# hw_tutorial.net
KiCad netlist of a schematic drawn in Altium Designer
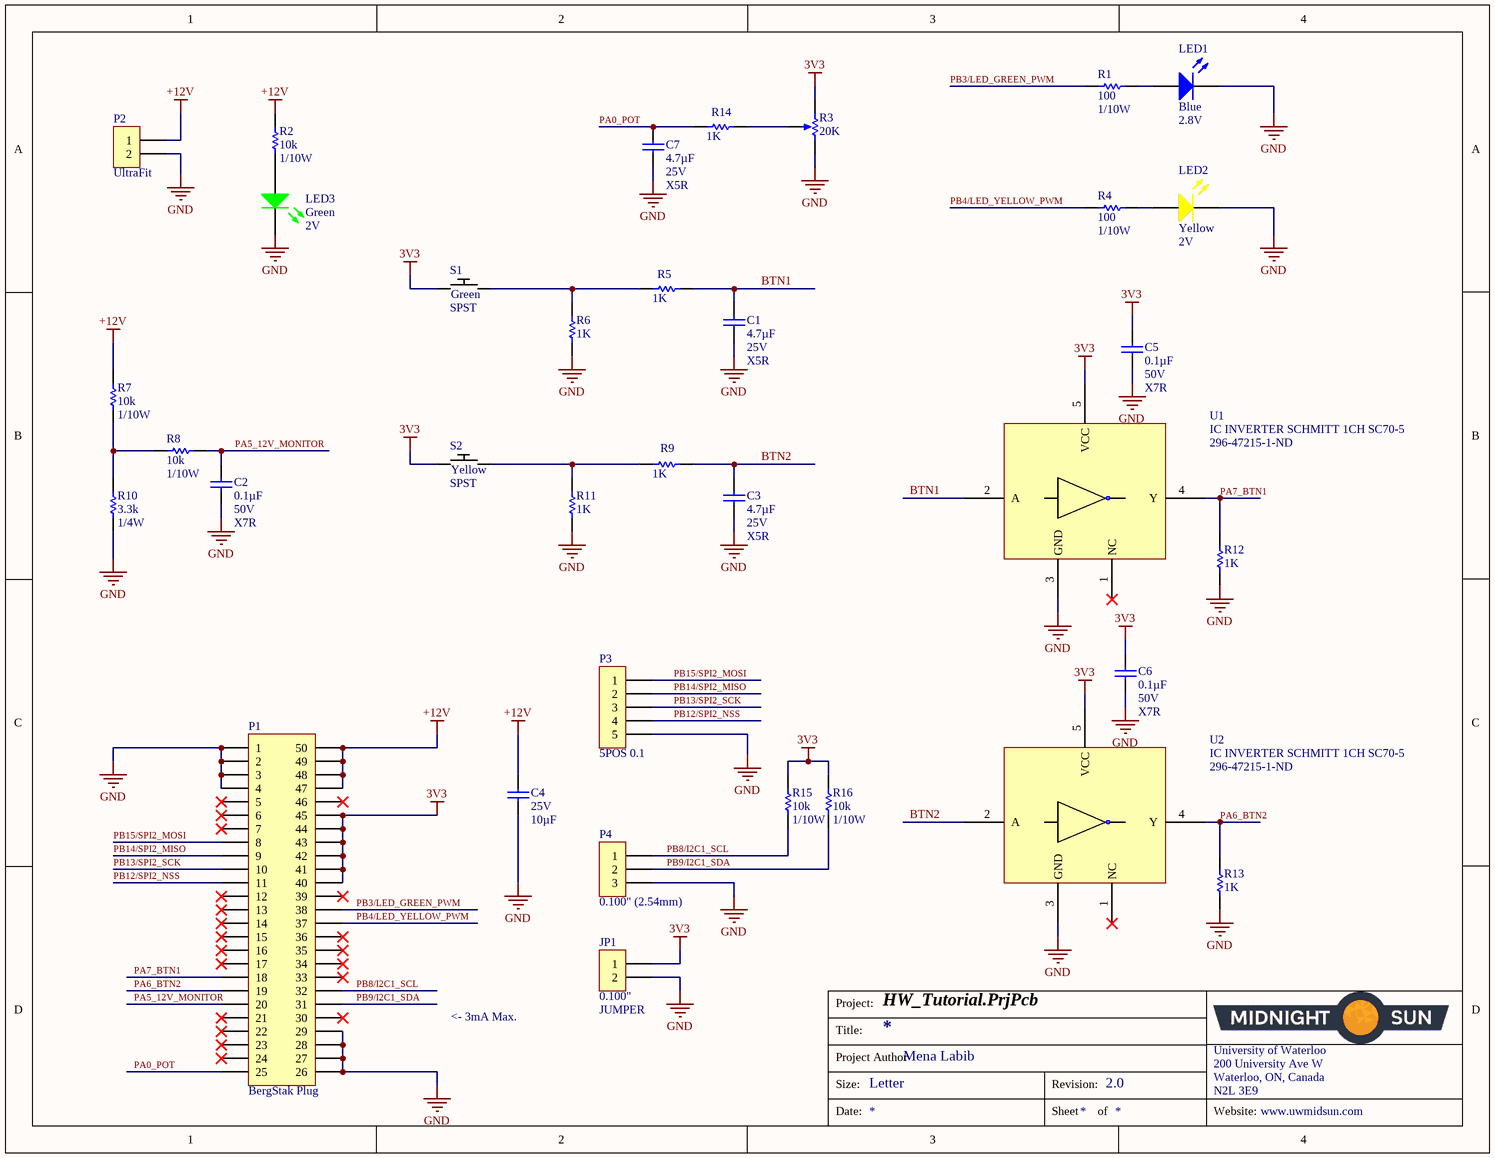
[diagram p0: hw_tutorial.SchDoc]

(export (version "E")
  (design (tool "Eeschema 10.0.6"))
  (components
    (comp (ref "C1")
      (value "CAP CER 4.7UF 25V 10% X5R 0603")
      (footprint "CAP, 0603")
      (description "4.7µF ±10% 25V Ceramic Capacitor X5R 0603 (1608 Metric)")
      (fields
        (field (name "TOLERANCE") "±10%")
        (field (name "CAPACITANCE") "4.7µF")
        (field (name "VOLTAGE") "25V")
        (field (name "TEMPERATURE COEFFICIENT") "X5R")
      )
      (libsource (lib "Schematic Diagrams") (part "CAP CER 4.7UF 25V 10% X5R 0603"))
    )
    (comp (ref "C2")
      (value "CAP CER 0.1UF 50V 10% X7R 0603")
      (footprint "CAP, 0603")
      (description "0.10µF ±10% 50V Ceramic Capacitor X7R 0603 (1608 Metric)")
      (fields
        (field (name "TOLERANCE") "±10%")
        (field (name "CAPACITANCE") "0.1µF")
        (field (name "VOLTAGE") "50V")
        (field (name "TEMPERATURE COEFFICIENT") "X7R")
      )
      (libsource (lib "Schematic Diagrams") (part "CAP CER 0.1UF 50V 10% X7R 0603"))
    )
    (comp (ref "C3")
      (value "CAP CER 4.7UF 25V 10% X5R 0603")
      (footprint "CAP, 0603")
      (description "4.7µF ±10% 25V Ceramic Capacitor X5R 0603 (1608 Metric)")
      (fields
        (field (name "TOLERANCE") "±10%")
        (field (name "CAPACITANCE") "4.7µF")
        (field (name "VOLTAGE") "25V")
        (field (name "TEMPERATURE COEFFICIENT") "X5R")
      )
      (libsource (lib "Schematic Diagrams") (part "CAP CER 4.7UF 25V 10% X5R 0603"))
    )
    (comp (ref "C4")
      (value "CAP CER 10uF 25V 10% X5R 0805")
      (footprint "CAP, 0805")
      (description "10µF ±10% 25V Ceramic Capacitor X5R 0805 (2012 Metric)")
      (fields
        (field (name "MANUFACTURER") "Murata Electronics North America")
        (field (name "MANUFACTURER PART NUMBER") "GRM21BR61E106KA73L")
        (field (name "VOLTAGE - RATED") "25V")
        (field (name "CAPACITANCE") "10µF")
      )
      (libsource (lib "Schematic Diagrams") (part "CAP CER 10uF 25V 10% X5R 0805"))
    )
    (comp (ref "C5")
      (value "CAP CER 0.1UF 50V 10% X7R 0603")
      (footprint "CAP, 0603")
      (description "0.10µF ±10% 50V Ceramic Capacitor X7R 0603 (1608 Metric)")
      (fields
        (field (name "TOLERANCE") "±10%")
        (field (name "CAPACITANCE") "0.1µF")
        (field (name "VOLTAGE") "50V")
        (field (name "TEMPERATURE COEFFICIENT") "X7R")
      )
      (libsource (lib "Schematic Diagrams") (part "CAP CER 0.1UF 50V 10% X7R 0603"))
    )
    (comp (ref "C6")
      (value "CAP CER 0.1UF 50V 10% X7R 0603")
      (footprint "CAP, 0603")
      (description "0.10µF ±10% 50V Ceramic Capacitor X7R 0603 (1608 Metric)")
      (fields
        (field (name "TOLERANCE") "±10%")
        (field (name "CAPACITANCE") "0.1µF")
        (field (name "VOLTAGE") "50V")
        (field (name "TEMPERATURE COEFFICIENT") "X7R")
      )
      (libsource (lib "Schematic Diagrams") (part "CAP CER 0.1UF 50V 10% X7R 0603"))
    )
    (comp (ref "C7")
      (value "CAP CER 4.7UF 25V 10% X5R 0603")
      (footprint "CAP, 0603")
      (description "4.7µF ±10% 25V Ceramic Capacitor X5R 0603 (1608 Metric)")
      (fields
        (field (name "TOLERANCE") "±10%")
        (field (name "CAPACITANCE") "4.7µF")
        (field (name "VOLTAGE") "25V")
        (field (name "TEMPERATURE COEFFICIENT") "X5R")
      )
      (libsource (lib "Schematic Diagrams") (part "CAP CER 4.7UF 25V 10% X5R 0603"))
    )
    (comp (ref "JP1")
      (value "JUMPER")
      (footprint "CONN, 2POS JUMPER 0.1\"")
      (description "2 Positions Header Connector Through Hole Gold")
      (fields
        (field (name "MANUFACTURER") "Omron Electronics Inc-EMC Div")
        (field (name "MANUFACTURER PART NUMBER") "XG8T-0231")
        (field (name "ROW SPACING - MATING") "0.100\"")
        (field (name "TYPE") "JUMPER")
      )
      (libsource (lib "Schematic Diagrams") (part "CONN 2POS JUMPER 0.1{dblquote}"))
    )
    (comp (ref "LED1")
      (value "LED BLUE CLEAR 2.8V 0603")
      (footprint "LED_0603")
      (description "Blue 470nm LED Indication - Discrete 2.8V 0603 (1608 Metric)")
      (fields (field (name "COLOR") "Blue") (field (name "VOLTAGE - FORWARD (VF) (TYP)") "2.8V"))
      (libsource (lib "Schematic Diagrams") (part "LED BLUE CLEAR 2.8V 0603"))
    )
    (comp (ref "LED2")
      (value "LED YELLOW CLEAR 2.1V 0603")
      (footprint "LED_0603")
      (description "Yellow 590nm LED Indication - Discrete 2V 0603 (1608 Metric)")
      (fields
        (field (name "MANUFACTURER") "Wurth Electronics Inc.")
        (field (name "MANUFACTURER PART NUMBER") "150060YS75000")
        (field (name "COLOR") "Yellow")
        (field (name "VOLTAGE - FORWARD (VF) (TYP)") "2V")
      )
      (libsource (lib "Schematic Diagrams") (part "LED YELLOW CLEAR 2.1V 0603"))
    )
    (comp (ref "LED3")
      (value "LED GREEN CLEAR 2V 0603")
      (footprint "LED_0603")
      (description "Green 572nm LED Indication - Discrete 2V 0603 (1608 Metric)")
      (fields
        (field (name "COLOR") "Green")
        (field (name "VOLTAGE - FORWARD (VF) (TYP)") "2V")
        (field (name "MANUFACTURER") "Wurth Electronics Inc.")
        (field (name "MANUFACTURER PART NUMBER") "150060VS75000")
      )
      (libsource (lib "Schematic Diagrams") (part "LED GREEN CLEAR 2V 0603"))
    )
    (comp (ref "P1")
      (value "CONN 50POS Bergstak Plug 0.02\"")
      (footprint "CONN, Bergstak 50 Pos Plug")
      (description "50 Position Connector Plug, Outer Shroud Contacts Surface Mount Gold")
      (fields (field (name "SERIES") "BergStak Plug"))
      (libsource (lib "Schematic Diagrams") (part "CONN 50POS Bergstak Plug 0.02{dblquote}"))
    )
    (comp (ref "P2")
      (value "CONN 2POS ULTRA-FIT 0.138\"")
      (footprint "CONN, 2POS ULTRA-FIT")
      (description "2 Positions Header, Shrouded Connector 0.138\" (3.50mm) Through Hole Gold")
      (fields (field (name "VOLTAGE") "400V") (field (name "SERIES") "UltraFit"))
      (libsource (lib "Schematic Diagrams") (part "CONN 2POS ULTRA-FIT 0.138{dblquote}"))
    )
    (comp (ref "P3")
      (value "5POS 0.1")
      (footprint "CONN, 5POS HEADR 0.1\"")
      (description "5 Positions Header, Breakaway Connector 0.100\" (2.54mm) Through Hole Tin")
      (libsource (lib "Schematic Diagrams") (part "CONN 5POS HEADR MALE 0.1in"))
    )
    (comp (ref "P4")
      (value "CONN 3POS HEADR MALE 0.1\"")
      (footprint "CONN, 3POS 0.100\" Header, 1 ROW")
      (description "3 Positions Header Connector 0.100\" (2.54mm) Through Hole Gold")
      (fields (field (name "VOLTAGE") "250V") (field (name "PITCH - MATING") "0.100\" (2.54mm)"))
      (libsource (lib "Schematic Diagrams") (part "CONN 3POS HEADR MALE 0.1{dblquote}"))
    )
    (comp (ref "R1")
      (value "RES 100 OHM 1% 1/10W 0603")
      (footprint "RES, 0603")
      (description "100 Ohm ±1% 0.1W, 1/10W Chip Resistor 0603 (1608 Metric) Moisture Resistant Thick Film")
      (fields
        (field (name "TOLERANCE") "±1%")
        (field (name "RESISTANCE") "100")
        (field (name "POWER") "1/10W")
      )
      (libsource (lib "Schematic Diagrams") (part "RES 100 OHM 1% 1/10W 0603"))
    )
    (comp (ref "R2")
      (value "RES 10K OHM 1% 1/10W 0603")
      (footprint "RES, 0603")
      (description "RES SMD 10K OHM 1% 1/10W 0603")
      (fields
        (field (name "TOLERANCE") "±1%")
        (field (name "RESISTANCE") "10k")
        (field (name "POWER") "1/10W")
      )
      (libsource (lib "Schematic Diagrams") (part "RES 10K OHM 1% 1/10W 0603"))
    )
    (comp (ref "R3")
      (value "20K")
      (footprint "20K POT")
      (description "20k Ohm 0.25W, 1/4W Gull Wing Surface Mount Trimmer Potentiometer")
      (fields (field (name "POWER") "1/4W") (field (name "MANUFACTURE PART NUMBER") "23BR20KLFTR"))
      (libsource (lib "Schematic Diagrams") (part "POT 20k OHM 20% 1/4W"))
    )
    (comp (ref "R4")
      (value "RES 100 OHM 1% 1/10W 0603")
      (footprint "RES, 0603")
      (description "100 Ohm ±1% 0.1W, 1/10W Chip Resistor 0603 (1608 Metric) Moisture Resistant Thick Film")
      (fields
        (field (name "TOLERANCE") "±1%")
        (field (name "RESISTANCE") "100")
        (field (name "POWER") "1/10W")
      )
      (libsource (lib "Schematic Diagrams") (part "RES 100 OHM 1% 1/10W 0603"))
    )
    (comp (ref "R5")
      (value "1K")
      (footprint "RES, 0603")
      (description "1k Ohm ±5% 0.1W, 1/10W Chip Resistor 0603 (1608 Metric)")
      (fields
        (field (name "MANUFACTURER") "Yageo")
        (field (name "MANUFACTURER PART NUMBER") "RC0603JR-071KL")
      )
      (libsource (lib "Schematic Diagrams") (part "RES 1K OHM 5% 1/10W 0603"))
    )
    (comp (ref "R6")
      (value "1K")
      (footprint "RES, 0603")
      (description "1k Ohm ±5% 0.1W, 1/10W Chip Resistor 0603 (1608 Metric)")
      (fields
        (field (name "MANUFACTURER") "Yageo")
        (field (name "MANUFACTURER PART NUMBER") "RC0603JR-071KL")
      )
      (libsource (lib "Schematic Diagrams") (part "RES 1K OHM 5% 1/10W 0603"))
    )
    (comp (ref "R7")
      (value "RES 10K OHM 1% 1/10W 0603")
      (footprint "RES, 0603")
      (description "RES SMD 10K OHM 1% 1/10W 0603")
      (fields
        (field (name "TOLERANCE") "±1%")
        (field (name "RESISTANCE") "10k")
        (field (name "POWER") "1/10W")
      )
      (libsource (lib "Schematic Diagrams") (part "RES 10K OHM 1% 1/10W 0603"))
    )
    (comp (ref "R8")
      (value "RES 10K OHM 1% 1/10W 0603")
      (footprint "RES, 0603")
      (description "RES SMD 10K OHM 1% 1/10W 0603")
      (fields
        (field (name "TOLERANCE") "±1%")
        (field (name "RESISTANCE") "10k")
        (field (name "POWER") "1/10W")
      )
      (libsource (lib "Schematic Diagrams") (part "RES 10K OHM 1% 1/10W 0603"))
    )
    (comp (ref "R9")
      (value "1K")
      (footprint "RES, 0603")
      (description "1k Ohm ±5% 0.1W, 1/10W Chip Resistor 0603 (1608 Metric)")
      (fields
        (field (name "MANUFACTURER") "Yageo")
        (field (name "MANUFACTURER PART NUMBER") "RC0603JR-071KL")
      )
      (libsource (lib "Schematic Diagrams") (part "RES 1K OHM 5% 1/10W 0603"))
    )
    (comp (ref "R10")
      (value "RES 3.3K OHM 1% 1/4W 0603")
      (footprint "RES, 0603")
      (fields
        (field (name "TOLERANCE") "±1%")
        (field (name "RESISTANCE") "3.3k")
        (field (name "POWER") "1/4W")
      )
      (libsource (lib "Schematic Diagrams") (part "RES 3.3K OHM 1% 1/4W 0603"))
    )
    (comp (ref "R11")
      (value "1K")
      (footprint "RES, 0603")
      (description "1k Ohm ±5% 0.1W, 1/10W Chip Resistor 0603 (1608 Metric)")
      (fields
        (field (name "MANUFACTURER") "Yageo")
        (field (name "MANUFACTURER PART NUMBER") "RC0603JR-071KL")
      )
      (libsource (lib "Schematic Diagrams") (part "RES 1K OHM 5% 1/10W 0603"))
    )
    (comp (ref "R12")
      (value "1K")
      (footprint "RES, 0603")
      (description "1k Ohm ±5% 0.1W, 1/10W Chip Resistor 0603 (1608 Metric)")
      (fields
        (field (name "MANUFACTURER") "Yageo")
        (field (name "MANUFACTURER PART NUMBER") "RC0603JR-071KL")
      )
      (libsource (lib "Schematic Diagrams") (part "RES 1K OHM 5% 1/10W 0603"))
    )
    (comp (ref "R13")
      (value "1K")
      (footprint "RES, 0603")
      (description "1k Ohm ±5% 0.1W, 1/10W Chip Resistor 0603 (1608 Metric)")
      (fields
        (field (name "MANUFACTURER") "Yageo")
        (field (name "MANUFACTURER PART NUMBER") "RC0603JR-071KL")
      )
      (libsource (lib "Schematic Diagrams") (part "RES 1K OHM 5% 1/10W 0603"))
    )
    (comp (ref "R14")
      (value "1K")
      (footprint "RES, 0603")
      (description "1k Ohm ±5% 0.1W, 1/10W Chip Resistor 0603 (1608 Metric)")
      (fields
        (field (name "MANUFACTURER") "Yageo")
        (field (name "MANUFACTURER PART NUMBER") "RC0603JR-071KL")
      )
      (libsource (lib "Schematic Diagrams") (part "RES 1K OHM 5% 1/10W 0603"))
    )
    (comp (ref "R15")
      (value "RES 10K OHM 1% 1/10W 0603")
      (footprint "RES, 0603")
      (description "RES SMD 10K OHM 1% 1/10W 0603")
      (fields
        (field (name "TOLERANCE") "±1%")
        (field (name "RESISTANCE") "10k")
        (field (name "POWER") "1/10W")
      )
      (libsource (lib "Schematic Diagrams") (part "RES 10K OHM 1% 1/10W 0603"))
    )
    (comp (ref "R16")
      (value "RES 10K OHM 1% 1/10W 0603")
      (footprint "RES, 0603")
      (description "RES SMD 10K OHM 1% 1/10W 0603")
      (fields
        (field (name "TOLERANCE") "±1%")
        (field (name "RESISTANCE") "10k")
        (field (name "POWER") "1/10W")
      )
      (libsource (lib "Schematic Diagrams") (part "RES 10K OHM 1% 1/10W 0603"))
    )
    (comp (ref "S1")
      (value "SPST")
      (footprint "SW SPST D6 SERIES GREEN")
      (description "Pushbutton Switch SPST-NO Keyswitch Through Hole D6 Series Green")
      (fields (field (name "MANUFACTURER") "C&K") (field (name "MANUFACTURER PART NUMBER") "D6R50 F1 LFS"))
      (libsource (lib "Schematic Diagrams") (part "SW SPST-NO 0.1A 32V D6 Series Green"))
    )
    (comp (ref "S2")
      (value "SPST")
      (footprint "SW SPST D6 SERIES YELLOW")
      (description "Pushbutton Switch SPST-NO Keyswitch Through Hole D6 Series Yellow")
      (fields (field (name "MANUFACTURER") "C&K") (field (name "MANUFACTURER PART NUMBER") "D6R30 F1 LFS"))
      (libsource (lib "Schematic Diagrams") (part "SW SPST-NO 0.1A 32V D6 Series Yellow"))
    )
    (comp (ref "U1")
      (value "IC INVERTER SCHMITT 1CH SC70-5")
      (footprint "IC INVERTER SCHMITT 1CH SC70-5")
      (description "Inverter IC 1 Channel Schmitt Trigger SC-70-5")
      (fields
        (field (name "MANUFACTURER") "STMicroelectronics")
        (field (name "MANUFACTURER PART NUMBER") "M74HC14YTTR")
        (field (name "SUPPLIER PART NUMBER 1") "296-47215-1-ND")
      )
      (libsource (lib "Schematic Diagrams") (part "IC INVERTER SCHMITT 1CH SC70-5"))
    )
    (comp (ref "U2")
      (value "IC INVERTER SCHMITT 1CH SC70-5")
      (footprint "IC INVERTER SCHMITT 1CH SC70-5")
      (description "Inverter IC 1 Channel Schmitt Trigger SC-70-5")
      (fields
        (field (name "MANUFACTURER") "STMicroelectronics")
        (field (name "MANUFACTURER PART NUMBER") "M74HC14YTTR")
        (field (name "SUPPLIER PART NUMBER 1") "296-47215-1-ND")
      )
      (libsource (lib "Schematic Diagrams") (part "IC INVERTER SCHMITT 1CH SC70-5"))
    )
  )
  (nets
    (net (code "1") (name "+12V") (class "Default")
      (node (ref "C4") (pin "1") (pinfunction "1_1") (pintype "passive"))
      (node (ref "P1") (pin "47") (pinfunction "47_47") (pintype "passive"))
      (node (ref "P1") (pin "48") (pinfunction "48_48") (pintype "passive"))
      (node (ref "P1") (pin "49") (pinfunction "49_49") (pintype "passive"))
      (node (ref "P1") (pin "50") (pinfunction "50_50") (pintype "passive"))
      (node (ref "P2") (pin "1") (pinfunction "1_1") (pintype "passive"))
      (node (ref "R2") (pin "1") (pinfunction "1_1") (pintype "passive"))
      (node (ref "R7") (pin "1") (pinfunction "1_1") (pintype "passive"))
    )
    (net (code "2") (name "/BTN1") (class "Default")
      (node (ref "C1") (pin "1") (pinfunction "1_1") (pintype "passive"))
      (node (ref "R5") (pin "2") (pinfunction "2_2") (pintype "passive"))
      (node (ref "U1") (pin "2") (pinfunction "A_2") (pintype "passive"))
    )
    (net (code "3") (name "/BTN2") (class "Default")
      (node (ref "C3") (pin "1") (pinfunction "1_1") (pintype "passive"))
      (node (ref "R9") (pin "2") (pinfunction "2_2") (pintype "passive"))
      (node (ref "U2") (pin "2") (pinfunction "A_2") (pintype "passive"))
    )
    (net (code "4") (name "/PA0_POT") (class "Default")
      (node (ref "C7") (pin "1") (pinfunction "1_1") (pintype "passive"))
      (node (ref "P1") (pin "25") (pinfunction "25_25") (pintype "passive"))
      (node (ref "R14") (pin "1") (pinfunction "1_1") (pintype "passive"))
    )
    (net (code "5") (name "/PA5_12V_MONITOR") (class "Default")
      (node (ref "C2") (pin "1") (pinfunction "1_1") (pintype "passive"))
      (node (ref "P1") (pin "20") (pinfunction "20_20") (pintype "passive"))
      (node (ref "R8") (pin "2") (pinfunction "2_2") (pintype "passive"))
    )
    (net (code "6") (name "/PA6_BTN2") (class "Default")
      (node (ref "P1") (pin "19") (pinfunction "19_19") (pintype "passive"))
      (node (ref "R13") (pin "2") (pinfunction "2_2") (pintype "passive"))
      (node (ref "U2") (pin "4") (pinfunction "Y_4") (pintype "passive"))
    )
    (net (code "7") (name "/PA7_BTN1") (class "Default")
      (node (ref "P1") (pin "18") (pinfunction "18_18") (pintype "passive"))
      (node (ref "R12") (pin "2") (pinfunction "2_2") (pintype "passive"))
      (node (ref "U1") (pin "4") (pinfunction "Y_4") (pintype "passive"))
    )
    (net (code "8") (name "/PB3{slash}LED_GREEN_PWM") (class "Default")
      (node (ref "P1") (pin "38") (pinfunction "38_38") (pintype "passive"))
      (node (ref "R1") (pin "1") (pinfunction "1_1") (pintype "passive"))
    )
    (net (code "9") (name "/PB4{slash}LED_YELLOW_PWM") (class "Default")
      (node (ref "P1") (pin "37") (pinfunction "37_37") (pintype "passive"))
      (node (ref "R4") (pin "1") (pinfunction "1_1") (pintype "passive"))
    )
    (net (code "10") (name "/PB8{slash}I2C1_SCL") (class "Default")
      (node (ref "P1") (pin "32") (pinfunction "32_32") (pintype "passive"))
      (node (ref "P4") (pin "1") (pinfunction "1_1") (pintype "passive"))
      (node (ref "R15") (pin "2") (pinfunction "2_2") (pintype "passive"))
    )
    (net (code "11") (name "/PB9{slash}I2C1_SDA") (class "Default")
      (node (ref "P1") (pin "31") (pinfunction "31_31") (pintype "passive"))
      (node (ref "P4") (pin "2") (pinfunction "2_2") (pintype "passive"))
      (node (ref "R16") (pin "2") (pinfunction "2_2") (pintype "passive"))
    )
    (net (code "12") (name "/PB12{slash}SPI2_NSS") (class "Default")
      (node (ref "P1") (pin "11") (pinfunction "11_11") (pintype "passive"))
      (node (ref "P3") (pin "4") (pinfunction "4_4") (pintype "passive"))
    )
    (net (code "13") (name "/PB13{slash}SPI2_SCK") (class "Default")
      (node (ref "P1") (pin "10") (pinfunction "10_10") (pintype "passive"))
      (node (ref "P3") (pin "3") (pinfunction "3_3") (pintype "passive"))
    )
    (net (code "14") (name "/PB14{slash}SPI2_MISO") (class "Default")
      (node (ref "P1") (pin "9") (pinfunction "9_9") (pintype "passive"))
      (node (ref "P3") (pin "2") (pinfunction "2_2") (pintype "passive"))
    )
    (net (code "15") (name "/PB15{slash}SPI2_MOSI") (class "Default")
      (node (ref "P1") (pin "8") (pinfunction "8_8") (pintype "passive"))
      (node (ref "P3") (pin "1") (pinfunction "1_1") (pintype "passive"))
    )
    (net (code "16") (name "3V3") (class "Default")
      (node (ref "C5") (pin "1") (pinfunction "1_1") (pintype "passive"))
      (node (ref "C6") (pin "1") (pinfunction "1_1") (pintype "passive"))
      (node (ref "JP1") (pin "1") (pinfunction "1_1") (pintype "passive"))
      (node (ref "P1") (pin "40") (pinfunction "40_40") (pintype "passive"))
      (node (ref "P1") (pin "41") (pinfunction "41_41") (pintype "passive"))
      (node (ref "P1") (pin "42") (pinfunction "42_42") (pintype "passive"))
      (node (ref "P1") (pin "43") (pinfunction "43_43") (pintype "passive"))
      (node (ref "P1") (pin "44") (pinfunction "44_44") (pintype "passive"))
      (node (ref "P1") (pin "45") (pinfunction "45_45") (pintype "passive"))
      (node (ref "R15") (pin "1") (pinfunction "1_1") (pintype "passive"))
      (node (ref "R16") (pin "1") (pinfunction "1_1") (pintype "passive"))
      (node (ref "R3") (pin "1") (pinfunction "TOP_1") (pintype "passive"))
      (node (ref "S1") (pin "1") (pinfunction "1_1") (pintype "passive"))
      (node (ref "S2") (pin "1") (pinfunction "1_1") (pintype "passive"))
      (node (ref "U1") (pin "5") (pinfunction "VCC_5") (pintype "passive"))
      (node (ref "U2") (pin "5") (pinfunction "VCC_5") (pintype "passive"))
    )
    (net (code "17") (name "GND") (class "Default")
      (node (ref "C1") (pin "2") (pinfunction "2_2") (pintype "passive"))
      (node (ref "C2") (pin "2") (pinfunction "2_2") (pintype "passive"))
      (node (ref "C3") (pin "2") (pinfunction "2_2") (pintype "passive"))
      (node (ref "C4") (pin "2") (pinfunction "2_2") (pintype "passive"))
      (node (ref "C5") (pin "2") (pinfunction "2_2") (pintype "passive"))
      (node (ref "C6") (pin "2") (pinfunction "2_2") (pintype "passive"))
      (node (ref "C7") (pin "2") (pinfunction "2_2") (pintype "passive"))
      (node (ref "JP1") (pin "2") (pinfunction "2_2") (pintype "passive"))
      (node (ref "LED1") (pin "2") (pinfunction "K_2") (pintype "passive"))
      (node (ref "LED2") (pin "2") (pinfunction "K_2") (pintype "passive"))
      (node (ref "LED3") (pin "2") (pinfunction "K_2") (pintype "passive"))
      (node (ref "P1") (pin "1") (pinfunction "1_1") (pintype "passive"))
      (node (ref "P1") (pin "2") (pinfunction "2_2") (pintype "passive"))
      (node (ref "P1") (pin "26") (pinfunction "26_26") (pintype "passive"))
      (node (ref "P1") (pin "27") (pinfunction "27_27") (pintype "passive"))
      (node (ref "P1") (pin "28") (pinfunction "28_28") (pintype "passive"))
      (node (ref "P1") (pin "29") (pinfunction "29_29") (pintype "passive"))
      (node (ref "P1") (pin "3") (pinfunction "3_3") (pintype "passive"))
      (node (ref "P1") (pin "4") (pinfunction "4_4") (pintype "passive"))
      (node (ref "P2") (pin "2") (pinfunction "2_2") (pintype "passive"))
      (node (ref "P3") (pin "5") (pinfunction "5_5") (pintype "passive"))
      (node (ref "P4") (pin "3") (pinfunction "3_3") (pintype "passive"))
      (node (ref "R10") (pin "2") (pinfunction "2_2") (pintype "passive"))
      (node (ref "R11") (pin "1") (pinfunction "1_1") (pintype "passive"))
      (node (ref "R12") (pin "1") (pinfunction "1_1") (pintype "passive"))
      (node (ref "R13") (pin "1") (pinfunction "1_1") (pintype "passive"))
      (node (ref "R3") (pin "3") (pinfunction "BOT_3") (pintype "passive"))
      (node (ref "R6") (pin "1") (pinfunction "1_1") (pintype "passive"))
      (node (ref "U1") (pin "3") (pinfunction "GND_3") (pintype "passive"))
      (node (ref "U2") (pin "3") (pinfunction "GND_3") (pintype "passive"))
    )
    (net (code "18") (name "Net-(LED1-A)") (class "Default")
      (node (ref "LED1") (pin "1") (pinfunction "A_1") (pintype "passive"))
      (node (ref "R1") (pin "2") (pinfunction "2_2") (pintype "passive"))
    )
    (net (code "19") (name "Net-(LED2-A)") (class "Default")
      (node (ref "LED2") (pin "1") (pinfunction "A_1") (pintype "passive"))
      (node (ref "R4") (pin "2") (pinfunction "2_2") (pintype "passive"))
    )
    (net (code "20") (name "Net-(LED3-A)") (class "Default")
      (node (ref "LED3") (pin "1") (pinfunction "A_1") (pintype "passive"))
      (node (ref "R2") (pin "2") (pinfunction "2_2") (pintype "passive"))
    )
    (net (code "21") (name "Net-(R3-TAP)") (class "Default")
      (node (ref "R14") (pin "2") (pinfunction "2_2") (pintype "passive"))
      (node (ref "R3") (pin "2") (pinfunction "TAP_2") (pintype "passive"))
    )
    (net (code "22") (name "Net-(R5-Pad1)") (class "Default")
      (node (ref "R5") (pin "1") (pinfunction "1_1") (pintype "passive"))
      (node (ref "R6") (pin "2") (pinfunction "2_2") (pintype "passive"))
      (node (ref "S1") (pin "2") (pinfunction "2_2") (pintype "passive"))
    )
    (net (code "23") (name "Net-(R10-Pad1)") (class "Default")
      (node (ref "R10") (pin "1") (pinfunction "1_1") (pintype "passive"))
      (node (ref "R7") (pin "2") (pinfunction "2_2") (pintype "passive"))
      (node (ref "R8") (pin "1") (pinfunction "1_1") (pintype "passive"))
    )
    (net (code "24") (name "Net-(R11-Pad2)") (class "Default")
      (node (ref "R11") (pin "2") (pinfunction "2_2") (pintype "passive"))
      (node (ref "R9") (pin "1") (pinfunction "1_1") (pintype "passive"))
      (node (ref "S2") (pin "2") (pinfunction "2_2") (pintype "passive"))
    )
    (net (code "25") (name "unconnected-(P1-Pad5)") (class "Default")
      (node (ref "P1") (pin "5") (pinfunction "5_5") (pintype "passive+no_connect"))
    )
    (net (code "26") (name "unconnected-(P1-Pad6)") (class "Default")
      (node (ref "P1") (pin "6") (pinfunction "6_6") (pintype "passive+no_connect"))
    )
    (net (code "27") (name "unconnected-(P1-Pad7)") (class "Default")
      (node (ref "P1") (pin "7") (pinfunction "7_7") (pintype "passive+no_connect"))
    )
    (net (code "28") (name "unconnected-(P1-Pad12)") (class "Default")
      (node (ref "P1") (pin "12") (pinfunction "12_12") (pintype "passive+no_connect"))
    )
    (net (code "29") (name "unconnected-(P1-Pad13)") (class "Default")
      (node (ref "P1") (pin "13") (pinfunction "13_13") (pintype "passive+no_connect"))
    )
    (net (code "30") (name "unconnected-(P1-Pad14)") (class "Default")
      (node (ref "P1") (pin "14") (pinfunction "14_14") (pintype "passive+no_connect"))
    )
    (net (code "31") (name "unconnected-(P1-Pad15)") (class "Default")
      (node (ref "P1") (pin "15") (pinfunction "15_15") (pintype "passive+no_connect"))
    )
    (net (code "32") (name "unconnected-(P1-Pad16)") (class "Default")
      (node (ref "P1") (pin "16") (pinfunction "16_16") (pintype "passive+no_connect"))
    )
    (net (code "33") (name "unconnected-(P1-Pad17)") (class "Default")
      (node (ref "P1") (pin "17") (pinfunction "17_17") (pintype "passive+no_connect"))
    )
    (net (code "34") (name "unconnected-(P1-Pad21)") (class "Default")
      (node (ref "P1") (pin "21") (pinfunction "21_21") (pintype "passive+no_connect"))
    )
    (net (code "35") (name "unconnected-(P1-Pad22)") (class "Default")
      (node (ref "P1") (pin "22") (pinfunction "22_22") (pintype "passive+no_connect"))
    )
    (net (code "36") (name "unconnected-(P1-Pad23)") (class "Default")
      (node (ref "P1") (pin "23") (pinfunction "23_23") (pintype "passive+no_connect"))
    )
    (net (code "37") (name "unconnected-(P1-Pad24)") (class "Default")
      (node (ref "P1") (pin "24") (pinfunction "24_24") (pintype "passive+no_connect"))
    )
    (net (code "38") (name "unconnected-(P1-Pad30)") (class "Default")
      (node (ref "P1") (pin "30") (pinfunction "30_30") (pintype "passive+no_connect"))
    )
    (net (code "39") (name "unconnected-(P1-Pad33)") (class "Default")
      (node (ref "P1") (pin "33") (pinfunction "33_33") (pintype "passive+no_connect"))
    )
    (net (code "40") (name "unconnected-(P1-Pad34)") (class "Default")
      (node (ref "P1") (pin "34") (pinfunction "34_34") (pintype "passive+no_connect"))
    )
    (net (code "41") (name "unconnected-(P1-Pad35)") (class "Default")
      (node (ref "P1") (pin "35") (pinfunction "35_35") (pintype "passive+no_connect"))
    )
    (net (code "42") (name "unconnected-(P1-Pad36)") (class "Default")
      (node (ref "P1") (pin "36") (pinfunction "36_36") (pintype "passive+no_connect"))
    )
    (net (code "43") (name "unconnected-(P1-Pad39)") (class "Default")
      (node (ref "P1") (pin "39") (pinfunction "39_39") (pintype "passive+no_connect"))
    )
    (net (code "44") (name "unconnected-(P1-Pad46)") (class "Default")
      (node (ref "P1") (pin "46") (pinfunction "46_46") (pintype "passive+no_connect"))
    )
    (net (code "45") (name "unconnected-(U1-NC-Pad1)") (class "Default")
      (node (ref "U1") (pin "1") (pinfunction "NC_1") (pintype "passive+no_connect"))
    )
    (net (code "46") (name "unconnected-(U2-NC-Pad1)") (class "Default")
      (node (ref "U2") (pin "1") (pinfunction "NC_1") (pintype "passive+no_connect"))
    )
  )
)
